# pinout.net
KiCad netlist of a schematic drawn in Altium Designer
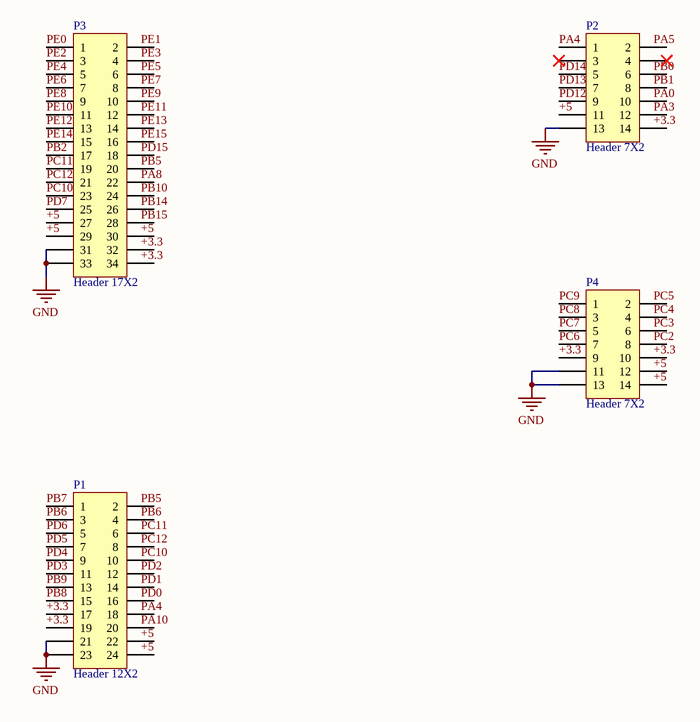
[diagram p0: pinout.SchDoc]

(export (version "E")
  (design (tool "Eeschema 10.0.6"))
  (components
    (comp (ref "P1")
      (value "Header 12X2")
      (footprint "IDC24S")
      (description "Header, 12-Pin, Dual row")
      (fields (field (name "PUBLISHER") "Altium Limited"))
      (libsource (lib "Miscellaneous Connectors") (part "Header 12X2"))
    )
    (comp (ref "P2")
      (value "Header 7X2")
      (footprint "IDC14S")
      (description "Header, 7-Pin, Dual row")
      (fields (field (name "PUBLISHER") "Altium Limited"))
      (libsource (lib "Miscellaneous Connectors") (part "Header 7X2"))
    )
    (comp (ref "P3")
      (value "Header 17X2")
      (footprint "IDC34S")
      (description "Header, 17-Pin, Dual row")
      (fields (field (name "PUBLISHER") "Altium Limited"))
      (libsource (lib "Miscellaneous Connectors") (part "Header 17X2"))
    )
    (comp (ref "P4")
      (value "Header 7X2")
      (footprint "IDC14S")
      (description "Header, 7-Pin, Dual row")
      (fields (field (name "PUBLISHER") "Altium Limited"))
      (libsource (lib "Miscellaneous Connectors") (part "Header 7X2"))
    )
  )
  (nets
    (net (code "1") (name "/+3.3") (class "Default")
      (node (ref "P1") (pin "17") (pinfunction "17_17") (pintype "passive"))
      (node (ref "P1") (pin "19") (pinfunction "19_19") (pintype "passive"))
      (node (ref "P4") (pin "9") (pinfunction "9_9") (pintype "passive"))
    )
    (net (code "2") (name "/+5") (class "Default")
      (node (ref "P2") (pin "11") (pinfunction "11_11") (pintype "passive"))
      (node (ref "P3") (pin "27") (pinfunction "27_27") (pintype "passive"))
      (node (ref "P3") (pin "29") (pinfunction "29_29") (pintype "passive"))
    )
    (net (code "5") (name "/PA4") (class "Default")
      (node (ref "P2") (pin "1") (pinfunction "1_1") (pintype "passive"))
    )
    (net (code "11") (name "/PB2") (class "Default")
      (node (ref "P3") (pin "17") (pinfunction "17_17") (pintype "passive"))
    )
    (net (code "13") (name "/PB6") (class "Default")
      (node (ref "P1") (pin "3") (pinfunction "3_3") (pintype "passive"))
    )
    (net (code "14") (name "/PB7") (class "Default")
      (node (ref "P1") (pin "1") (pinfunction "1_1") (pintype "passive"))
    )
    (net (code "15") (name "/PB8") (class "Default")
      (node (ref "P1") (pin "15") (pinfunction "15_15") (pintype "passive"))
    )
    (net (code "16") (name "/PB9") (class "Default")
      (node (ref "P1") (pin "13") (pinfunction "13_13") (pintype "passive"))
    )
    (net (code "24") (name "/PC6") (class "Default")
      (node (ref "P4") (pin "7") (pinfunction "7_7") (pintype "passive"))
    )
    (net (code "25") (name "/PC7") (class "Default")
      (node (ref "P4") (pin "5") (pinfunction "5_5") (pintype "passive"))
    )
    (net (code "26") (name "/PC8") (class "Default")
      (node (ref "P4") (pin "3") (pinfunction "3_3") (pintype "passive"))
    )
    (net (code "27") (name "/PC9") (class "Default")
      (node (ref "P4") (pin "1") (pinfunction "1_1") (pintype "passive"))
    )
    (net (code "28") (name "/PC10") (class "Default")
      (node (ref "P3") (pin "23") (pinfunction "23_23") (pintype "passive"))
    )
    (net (code "29") (name "/PC11") (class "Default")
      (node (ref "P3") (pin "19") (pinfunction "19_19") (pintype "passive"))
    )
    (net (code "30") (name "/PC12") (class "Default")
      (node (ref "P3") (pin "21") (pinfunction "21_21") (pintype "passive"))
    )
    (net (code "34") (name "/PD3") (class "Default")
      (node (ref "P1") (pin "11") (pinfunction "11_11") (pintype "passive"))
    )
    (net (code "35") (name "/PD4") (class "Default")
      (node (ref "P1") (pin "9") (pinfunction "9_9") (pintype "passive"))
    )
    (net (code "36") (name "/PD5") (class "Default")
      (node (ref "P1") (pin "7") (pinfunction "7_7") (pintype "passive"))
    )
    (net (code "37") (name "/PD6") (class "Default")
      (node (ref "P1") (pin "5") (pinfunction "5_5") (pintype "passive"))
    )
    (net (code "38") (name "/PD7") (class "Default")
      (node (ref "P3") (pin "25") (pinfunction "25_25") (pintype "passive"))
    )
    (net (code "39") (name "/PD12") (class "Default")
      (node (ref "P2") (pin "9") (pinfunction "9_9") (pintype "passive"))
    )
    (net (code "40") (name "/PD13") (class "Default")
      (node (ref "P2") (pin "7") (pinfunction "7_7") (pintype "passive"))
    )
    (net (code "41") (name "/PD14") (class "Default")
      (node (ref "P2") (pin "5") (pinfunction "5_5") (pintype "passive"))
    )
    (net (code "43") (name "/PE0") (class "Default")
      (node (ref "P3") (pin "1") (pinfunction "1_1") (pintype "passive"))
    )
    (net (code "45") (name "/PE2") (class "Default")
      (node (ref "P3") (pin "3") (pinfunction "3_3") (pintype "passive"))
    )
    (net (code "47") (name "/PE4") (class "Default")
      (node (ref "P3") (pin "5") (pinfunction "5_5") (pintype "passive"))
    )
    (net (code "49") (name "/PE6") (class "Default")
      (node (ref "P3") (pin "7") (pinfunction "7_7") (pintype "passive"))
    )
    (net (code "51") (name "/PE8") (class "Default")
      (node (ref "P3") (pin "9") (pinfunction "9_9") (pintype "passive"))
    )
    (net (code "53") (name "/PE10") (class "Default")
      (node (ref "P3") (pin "11") (pinfunction "11_11") (pintype "passive"))
    )
    (net (code "55") (name "/PE12") (class "Default")
      (node (ref "P3") (pin "13") (pinfunction "13_13") (pintype "passive"))
    )
    (net (code "57") (name "/PE14") (class "Default")
      (node (ref "P3") (pin "15") (pinfunction "15_15") (pintype "passive"))
    )
    (net (code "59") (name "GND") (class "Default")
      (node (ref "P1") (pin "21") (pinfunction "21_21") (pintype "passive"))
      (node (ref "P1") (pin "23") (pinfunction "23_23") (pintype "passive"))
      (node (ref "P2") (pin "13") (pinfunction "13_13") (pintype "passive"))
      (node (ref "P3") (pin "31") (pinfunction "31_31") (pintype "passive"))
      (node (ref "P3") (pin "33") (pinfunction "33_33") (pintype "passive"))
      (node (ref "P4") (pin "11") (pinfunction "11_11") (pintype "passive"))
      (node (ref "P4") (pin "13") (pinfunction "13_13") (pintype "passive"))
    )
    (net (code "60") (name "unconnected-(P1-Pad2)") (class "Default")
      (node (ref "P1") (pin "2") (pinfunction "2_2") (pintype "passive"))
    )
    (net (code "61") (name "unconnected-(P1-Pad4)") (class "Default")
      (node (ref "P1") (pin "4") (pinfunction "4_4") (pintype "passive"))
    )
    (net (code "62") (name "unconnected-(P1-Pad6)") (class "Default")
      (node (ref "P1") (pin "6") (pinfunction "6_6") (pintype "passive"))
    )
    (net (code "63") (name "unconnected-(P1-Pad8)") (class "Default")
      (node (ref "P1") (pin "8") (pinfunction "8_8") (pintype "passive"))
    )
    (net (code "64") (name "unconnected-(P1-Pad10)") (class "Default")
      (node (ref "P1") (pin "10") (pinfunction "10_10") (pintype "passive"))
    )
    (net (code "65") (name "unconnected-(P1-Pad12)") (class "Default")
      (node (ref "P1") (pin "12") (pinfunction "12_12") (pintype "passive"))
    )
    (net (code "66") (name "unconnected-(P1-Pad14)") (class "Default")
      (node (ref "P1") (pin "14") (pinfunction "14_14") (pintype "passive"))
    )
    (net (code "67") (name "unconnected-(P1-Pad16)") (class "Default")
      (node (ref "P1") (pin "16") (pinfunction "16_16") (pintype "passive"))
    )
    (net (code "68") (name "unconnected-(P1-Pad18)") (class "Default")
      (node (ref "P1") (pin "18") (pinfunction "18_18") (pintype "passive"))
    )
    (net (code "69") (name "unconnected-(P1-Pad20)") (class "Default")
      (node (ref "P1") (pin "20") (pinfunction "20_20") (pintype "passive"))
    )
    (net (code "70") (name "unconnected-(P1-Pad22)") (class "Default")
      (node (ref "P1") (pin "22") (pinfunction "22_22") (pintype "passive"))
    )
    (net (code "71") (name "unconnected-(P1-Pad24)") (class "Default")
      (node (ref "P1") (pin "24") (pinfunction "24_24") (pintype "passive"))
    )
    (net (code "72") (name "unconnected-(P2-Pad2)") (class "Default")
      (node (ref "P2") (pin "2") (pinfunction "2_2") (pintype "passive"))
    )
    (net (code "73") (name "unconnected-(P2-Pad3)") (class "Default")
      (node (ref "P2") (pin "3") (pinfunction "3_3") (pintype "passive+no_connect"))
    )
    (net (code "74") (name "unconnected-(P2-Pad4)") (class "Default")
      (node (ref "P2") (pin "4") (pinfunction "4_4") (pintype "passive+no_connect"))
    )
    (net (code "75") (name "unconnected-(P2-Pad6)") (class "Default")
      (node (ref "P2") (pin "6") (pinfunction "6_6") (pintype "passive"))
    )
    (net (code "76") (name "unconnected-(P2-Pad8)") (class "Default")
      (node (ref "P2") (pin "8") (pinfunction "8_8") (pintype "passive"))
    )
    (net (code "77") (name "unconnected-(P2-Pad10)") (class "Default")
      (node (ref "P2") (pin "10") (pinfunction "10_10") (pintype "passive"))
    )
    (net (code "78") (name "unconnected-(P2-Pad12)") (class "Default")
      (node (ref "P2") (pin "12") (pinfunction "12_12") (pintype "passive"))
    )
    (net (code "79") (name "unconnected-(P2-Pad14)") (class "Default")
      (node (ref "P2") (pin "14") (pinfunction "14_14") (pintype "passive"))
    )
    (net (code "80") (name "unconnected-(P3-Pad2)") (class "Default")
      (node (ref "P3") (pin "2") (pinfunction "2_2") (pintype "passive"))
    )
    (net (code "81") (name "unconnected-(P3-Pad4)") (class "Default")
      (node (ref "P3") (pin "4") (pinfunction "4_4") (pintype "passive"))
    )
    (net (code "82") (name "unconnected-(P3-Pad6)") (class "Default")
      (node (ref "P3") (pin "6") (pinfunction "6_6") (pintype "passive"))
    )
    (net (code "83") (name "unconnected-(P3-Pad8)") (class "Default")
      (node (ref "P3") (pin "8") (pinfunction "8_8") (pintype "passive"))
    )
    (net (code "84") (name "unconnected-(P3-Pad10)") (class "Default")
      (node (ref "P3") (pin "10") (pinfunction "10_10") (pintype "passive"))
    )
    (net (code "85") (name "unconnected-(P3-Pad12)") (class "Default")
      (node (ref "P3") (pin "12") (pinfunction "12_12") (pintype "passive"))
    )
    (net (code "86") (name "unconnected-(P3-Pad14)") (class "Default")
      (node (ref "P3") (pin "14") (pinfunction "14_14") (pintype "passive"))
    )
    (net (code "87") (name "unconnected-(P3-Pad16)") (class "Default")
      (node (ref "P3") (pin "16") (pinfunction "16_16") (pintype "passive"))
    )
    (net (code "88") (name "unconnected-(P3-Pad18)") (class "Default")
      (node (ref "P3") (pin "18") (pinfunction "18_18") (pintype "passive"))
    )
    (net (code "89") (name "unconnected-(P3-Pad20)") (class "Default")
      (node (ref "P3") (pin "20") (pinfunction "20_20") (pintype "passive"))
    )
    (net (code "90") (name "unconnected-(P3-Pad22)") (class "Default")
      (node (ref "P3") (pin "22") (pinfunction "22_22") (pintype "passive"))
    )
    (net (code "91") (name "unconnected-(P3-Pad24)") (class "Default")
      (node (ref "P3") (pin "24") (pinfunction "24_24") (pintype "passive"))
    )
    (net (code "92") (name "unconnected-(P3-Pad26)") (class "Default")
      (node (ref "P3") (pin "26") (pinfunction "26_26") (pintype "passive"))
    )
    (net (code "93") (name "unconnected-(P3-Pad28)") (class "Default")
      (node (ref "P3") (pin "28") (pinfunction "28_28") (pintype "passive"))
    )
    (net (code "94") (name "unconnected-(P3-Pad30)") (class "Default")
      (node (ref "P3") (pin "30") (pinfunction "30_30") (pintype "passive"))
    )
    (net (code "95") (name "unconnected-(P3-Pad32)") (class "Default")
      (node (ref "P3") (pin "32") (pinfunction "32_32") (pintype "passive"))
    )
    (net (code "96") (name "unconnected-(P3-Pad34)") (class "Default")
      (node (ref "P3") (pin "34") (pinfunction "34_34") (pintype "passive"))
    )
    (net (code "97") (name "unconnected-(P4-Pad2)") (class "Default")
      (node (ref "P4") (pin "2") (pinfunction "2_2") (pintype "passive"))
    )
    (net (code "98") (name "unconnected-(P4-Pad4)") (class "Default")
      (node (ref "P4") (pin "4") (pinfunction "4_4") (pintype "passive"))
    )
    (net (code "99") (name "unconnected-(P4-Pad6)") (class "Default")
      (node (ref "P4") (pin "6") (pinfunction "6_6") (pintype "passive"))
    )
    (net (code "100") (name "unconnected-(P4-Pad8)") (class "Default")
      (node (ref "P4") (pin "8") (pinfunction "8_8") (pintype "passive"))
    )
    (net (code "101") (name "unconnected-(P4-Pad10)") (class "Default")
      (node (ref "P4") (pin "10") (pinfunction "10_10") (pintype "passive"))
    )
    (net (code "102") (name "unconnected-(P4-Pad12)") (class "Default")
      (node (ref "P4") (pin "12") (pinfunction "12_12") (pintype "passive"))
    )
    (net (code "103") (name "unconnected-(P4-Pad14)") (class "Default")
      (node (ref "P4") (pin "14") (pinfunction "14_14") (pintype "passive"))
    )
  )
)
